# 10_-_Expansion_Connectors.net
KiCad netlist of a schematic drawn in Altium Designer
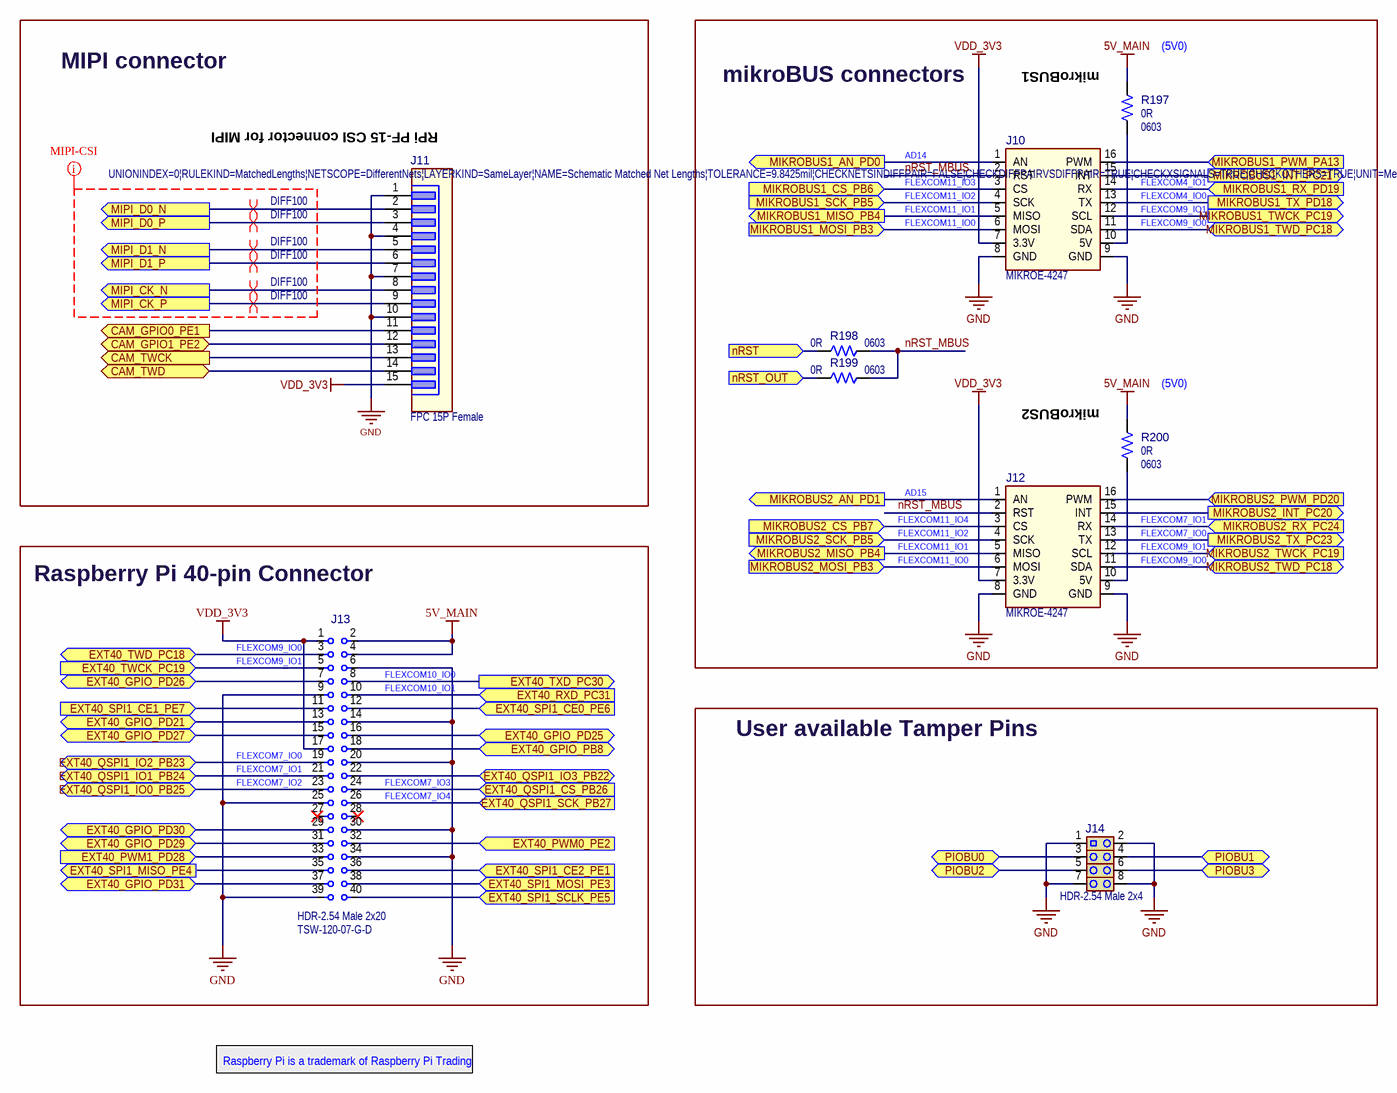
[diagram p0: 10 - Expansion Connectors.SchDoc]

(export (version "E")
  (design (tool "Eeschema 10.0.6"))
  (components
    (comp (ref "J10")
      (value "MIKROE-4247")
      (footprint "SOCKET_mikroBUS_F_2.54_2x8_V_25.4x21_original")
      (fields (field (name "Comment") "SOCKET mikroBUS HOST") (field (name "OWNER") "Dragos Danaila"))
      (libsource (lib "MCHP-CDB") (part "SOCKET mikroBUS HOST"))
    )
    (comp (ref "J11")
      (value "FPC 15P Female")
      (footprint "CON_FPC_1_FEMALE_1X15_SMD_TE_1-1734248-5")
      (fields
        (field (name "VOLTAGE") "125V")
        (field (name "Comment") "CON FPC 15pos")
        (field (name "OWNER") "Ilie Galan")
      )
      (libsource (lib "MCHP-CDB") (part "CON FPC 15pos"))
    )
    (comp (ref "J12")
      (value "MIKROE-4247")
      (footprint "SOCKET_mikroBUS_F_2.54_2x8_V_25.4x21_original")
      (fields (field (name "Comment") "SOCKET mikroBUS HOST") (field (name "OWNER") "Dragos Danaila"))
      (libsource (lib "MCHP-CDB") (part "SOCKET mikroBUS HOST"))
    )
    (comp (ref "J13")
      (value "HDR-2.54 Male 2x20")
      (footprint "HDR_M_2.54_2x20")
      (fields
        (field (name "MANUFACTURER PART NUMBER 1") "TSW-120-07-G-D")
        (field (name "Comment") "Header 2x20")
        (field (name "OWNER") "Stephen Humberd")
      )
      (libsource (lib "MCHP-CDB") (part "Header 2x20"))
    )
    (comp (ref "J14")
      (value "HDR-2.54 Male 2x4")
      (footprint "HDR_M_2.54_2x4_SMD")
      (fields (field (name "Comment") "Header 2x4") (field (name "OWNER") "Jamus Griego"))
      (libsource (lib "MCHP-CDB") (part "Header 2x4"))
    )
    (comp (ref "R197")
      (value "0R")
      (footprint "RES_C_0603")
      (description "Resistor")
      (fields (field (name "PACKAGE") "0603") (field (name "POWER") "1/10W"))
      (libsource (lib "MCHP-CDB") (part "Resistor"))
    )
    (comp (ref "R198")
      (value "0R")
      (footprint "RES_C_0603")
      (description "Resistor")
      (fields (field (name "PACKAGE") "0603") (field (name "POWER") "1/10W"))
      (libsource (lib "MCHP-CDB") (part "Resistor"))
    )
    (comp (ref "R199")
      (value "0R")
      (footprint "RES_C_0603")
      (description "Resistor")
      (fields (field (name "PACKAGE") "0603") (field (name "POWER") "1/10W"))
      (libsource (lib "MCHP-CDB") (part "Resistor"))
    )
    (comp (ref "R200")
      (value "0R")
      (footprint "RES_C_0603")
      (description "Resistor")
      (fields (field (name "PACKAGE") "0603") (field (name "POWER") "1/10W"))
      (libsource (lib "MCHP-CDB") (part "Resistor"))
    )
  )
  (nets
    (net (code "1") (name "/CAM_GPIO0_PE1") (class "Default")
      (node (ref "J11") (pin "11") (pinfunction "11_11") (pintype "passive"))
    )
    (net (code "2") (name "/CAM_GPIO1_PE2") (class "Default")
      (node (ref "J11") (pin "12") (pinfunction "12_12") (pintype "passive"))
    )
    (net (code "3") (name "/CAM_TWCK") (class "Default")
      (node (ref "J11") (pin "13") (pinfunction "13_13") (pintype "passive"))
    )
    (net (code "4") (name "/CAM_TWD") (class "Default")
      (node (ref "J11") (pin "14") (pinfunction "14_14") (pintype "passive"))
    )
    (net (code "5") (name "/EXT40_GPIO_PB8") (class "Default")
      (node (ref "J13") (pin "18") (pinfunction "18_18") (pintype "passive"))
    )
    (net (code "6") (name "/EXT40_GPIO_PD21") (class "Default")
      (node (ref "J13") (pin "13") (pinfunction "13_13") (pintype "passive"))
    )
    (net (code "7") (name "/EXT40_GPIO_PD25") (class "Default")
      (node (ref "J13") (pin "16") (pinfunction "16_16") (pintype "passive"))
    )
    (net (code "8") (name "/EXT40_GPIO_PD26") (class "Default")
      (node (ref "J13") (pin "7") (pinfunction "7_7") (pintype "passive"))
    )
    (net (code "9") (name "/EXT40_GPIO_PD27") (class "Default")
      (node (ref "J13") (pin "15") (pinfunction "15_15") (pintype "passive"))
    )
    (net (code "10") (name "/EXT40_GPIO_PD29") (class "Default")
      (node (ref "J13") (pin "31") (pinfunction "31_31") (pintype "passive"))
    )
    (net (code "11") (name "/EXT40_GPIO_PD30") (class "Default")
      (node (ref "J13") (pin "29") (pinfunction "29_29") (pintype "passive"))
    )
    (net (code "12") (name "/EXT40_GPIO_PD31") (class "Default")
      (node (ref "J13") (pin "37") (pinfunction "37_37") (pintype "passive"))
    )
    (net (code "13") (name "/EXT40_PWM0_PE2") (class "Default")
      (node (ref "J13") (pin "32") (pinfunction "32_32") (pintype "passive"))
    )
    (net (code "14") (name "/EXT40_PWM1_PD28") (class "Default")
      (node (ref "J13") (pin "33") (pinfunction "33_33") (pintype "passive"))
    )
    (net (code "15") (name "/EXT40_QSPI1_CS_PB26") (class "Default")
      (node (ref "J13") (pin "24") (pinfunction "24_24") (pintype "passive"))
    )
    (net (code "16") (name "/EXT40_QSPI1_IO0_PB25") (class "Default")
      (node (ref "J13") (pin "23") (pinfunction "23_23") (pintype "passive"))
    )
    (net (code "17") (name "/EXT40_QSPI1_IO1_PB24") (class "Default")
      (node (ref "J13") (pin "21") (pinfunction "21_21") (pintype "passive"))
    )
    (net (code "18") (name "/EXT40_QSPI1_IO2_PB23") (class "Default")
      (node (ref "J13") (pin "19") (pinfunction "19_19") (pintype "passive"))
    )
    (net (code "19") (name "/EXT40_QSPI1_IO3_PB22") (class "Default")
      (node (ref "J13") (pin "22") (pinfunction "22_22") (pintype "passive"))
    )
    (net (code "20") (name "/EXT40_QSPI1_SCK_PB27") (class "Default")
      (node (ref "J13") (pin "26") (pinfunction "26_26") (pintype "passive"))
    )
    (net (code "21") (name "/EXT40_RXD_PC31") (class "Default")
      (node (ref "J13") (pin "10") (pinfunction "10_10") (pintype "passive"))
    )
    (net (code "22") (name "/EXT40_SPI1_CE0_PE6") (class "Default")
      (node (ref "J13") (pin "12") (pinfunction "12_12") (pintype "passive"))
    )
    (net (code "23") (name "/EXT40_SPI1_CE1_PE7") (class "Default")
      (node (ref "J13") (pin "11") (pinfunction "11_11") (pintype "passive"))
    )
    (net (code "24") (name "/EXT40_SPI1_CE2_PE1") (class "Default")
      (node (ref "J13") (pin "36") (pinfunction "36_36") (pintype "passive"))
    )
    (net (code "25") (name "/EXT40_SPI1_MISO_PE4") (class "Default")
      (node (ref "J13") (pin "35") (pinfunction "35_35") (pintype "passive"))
    )
    (net (code "26") (name "/EXT40_SPI1_MOSI_PE3") (class "Default")
      (node (ref "J13") (pin "38") (pinfunction "38_38") (pintype "passive"))
    )
    (net (code "27") (name "/EXT40_SPI1_SCLK_PE5") (class "Default")
      (node (ref "J13") (pin "40") (pinfunction "40_40") (pintype "passive"))
    )
    (net (code "28") (name "/EXT40_TWCK_PC19") (class "Default")
      (node (ref "J13") (pin "5") (pinfunction "5_5") (pintype "passive"))
    )
    (net (code "29") (name "/EXT40_TWD_PC18") (class "Default")
      (node (ref "J13") (pin "3") (pinfunction "3_3") (pintype "passive"))
    )
    (net (code "30") (name "/EXT40_TXD_PC30") (class "Default")
      (node (ref "J13") (pin "8") (pinfunction "8_8") (pintype "passive"))
    )
    (net (code "31") (name "/MIKROBUS1_AN_PD0") (class "Default")
      (node (ref "J10") (pin "1") (pinfunction "AN_1") (pintype "passive"))
    )
    (net (code "32") (name "/MIKROBUS1_CS_PB6") (class "Default")
      (node (ref "J10") (pin "3") (pinfunction "CS_3") (pintype "passive"))
    )
    (net (code "33") (name "/MIKROBUS1_INT_PC21") (class "Default")
      (node (ref "J10") (pin "15") (pinfunction "INT_15") (pintype "passive"))
    )
    (net (code "34") (name "/MIKROBUS1_MISO_PB4") (class "Default")
      (node (ref "J10") (pin "5") (pinfunction "MISO_5") (pintype "passive"))
    )
    (net (code "35") (name "/MIKROBUS1_MOSI_PB3") (class "Default")
      (node (ref "J10") (pin "6") (pinfunction "MOSI_6") (pintype "passive"))
    )
    (net (code "36") (name "/MIKROBUS1_PWM_PA13") (class "Default")
      (node (ref "J10") (pin "16") (pinfunction "PWM_16") (pintype "passive"))
    )
    (net (code "37") (name "/MIKROBUS1_RX_PD19") (class "Default")
      (node (ref "J10") (pin "14") (pinfunction "RX_14") (pintype "passive"))
    )
    (net (code "38") (name "/MIKROBUS1_SCK_PB5") (class "Default")
      (node (ref "J10") (pin "4") (pinfunction "SCK_4") (pintype "passive"))
    )
    (net (code "39") (name "/MIKROBUS1_TWCK_PC19") (class "Default")
      (node (ref "J10") (pin "12") (pinfunction "SCL_12") (pintype "passive"))
    )
    (net (code "40") (name "/MIKROBUS1_TWD_PC18") (class "Default")
      (node (ref "J10") (pin "11") (pinfunction "SDA_11") (pintype "passive"))
    )
    (net (code "41") (name "/MIKROBUS1_TX_PD18") (class "Default")
      (node (ref "J10") (pin "13") (pinfunction "TX_13") (pintype "passive"))
    )
    (net (code "42") (name "/MIKROBUS2_AN_PD1") (class "Default")
      (node (ref "J12") (pin "1") (pinfunction "AN_1") (pintype "passive"))
    )
    (net (code "43") (name "/MIKROBUS2_CS_PB7") (class "Default")
      (node (ref "J12") (pin "3") (pinfunction "CS_3") (pintype "passive"))
    )
    (net (code "44") (name "/MIKROBUS2_INT_PC20") (class "Default")
      (node (ref "J12") (pin "15") (pinfunction "INT_15") (pintype "passive"))
    )
    (net (code "45") (name "/MIKROBUS2_MISO_PB4") (class "Default")
      (node (ref "J12") (pin "5") (pinfunction "MISO_5") (pintype "passive"))
    )
    (net (code "46") (name "/MIKROBUS2_MOSI_PB3") (class "Default")
      (node (ref "J12") (pin "6") (pinfunction "MOSI_6") (pintype "passive"))
    )
    (net (code "47") (name "/MIKROBUS2_PWM_PD20") (class "Default")
      (node (ref "J12") (pin "16") (pinfunction "PWM_16") (pintype "passive"))
    )
    (net (code "48") (name "/MIKROBUS2_RX_PC24") (class "Default")
      (node (ref "J12") (pin "14") (pinfunction "RX_14") (pintype "passive"))
    )
    (net (code "49") (name "/MIKROBUS2_SCK_PB5") (class "Default")
      (node (ref "J12") (pin "4") (pinfunction "SCK_4") (pintype "passive"))
    )
    (net (code "50") (name "/MIKROBUS2_TWCK_PC19") (class "Default")
      (node (ref "J12") (pin "12") (pinfunction "SCL_12") (pintype "passive"))
    )
    (net (code "51") (name "/MIKROBUS2_TWD_PC18") (class "Default")
      (node (ref "J12") (pin "11") (pinfunction "SDA_11") (pintype "passive"))
    )
    (net (code "52") (name "/MIKROBUS2_TX_PC23") (class "Default")
      (node (ref "J12") (pin "13") (pinfunction "TX_13") (pintype "passive"))
    )
    (net (code "53") (name "/MIPI_CK_N") (class "Default")
      (node (ref "J11") (pin "8") (pinfunction "8_8") (pintype "passive"))
    )
    (net (code "54") (name "/MIPI_CK_P") (class "Default")
      (node (ref "J11") (pin "9") (pinfunction "9_9") (pintype "passive"))
    )
    (net (code "55") (name "/MIPI_D0_N") (class "Default")
      (node (ref "J11") (pin "2") (pinfunction "2_2") (pintype "passive"))
    )
    (net (code "56") (name "/MIPI_D0_P") (class "Default")
      (node (ref "J11") (pin "3") (pinfunction "3_3") (pintype "passive"))
    )
    (net (code "57") (name "/MIPI_D1_N") (class "Default")
      (node (ref "J11") (pin "5") (pinfunction "5_5") (pintype "passive"))
    )
    (net (code "58") (name "/MIPI_D1_P") (class "Default")
      (node (ref "J11") (pin "6") (pinfunction "6_6") (pintype "passive"))
    )
    (net (code "59") (name "/PIOBU0") (class "Default")
      (node (ref "J14") (pin "3") (pinfunction "3_3") (pintype "passive"))
    )
    (net (code "60") (name "/PIOBU1") (class "Default")
      (node (ref "J14") (pin "4") (pinfunction "4_4") (pintype "passive"))
    )
    (net (code "61") (name "/PIOBU2") (class "Default")
      (node (ref "J14") (pin "5") (pinfunction "5_5") (pintype "passive"))
    )
    (net (code "62") (name "/PIOBU3") (class "Default")
      (node (ref "J14") (pin "6") (pinfunction "6_6") (pintype "passive"))
    )
    (net (code "63") (name "/nRST") (class "Default")
      (node (ref "R198") (pin "1") (pinfunction "1_1") (pintype "passive"))
    )
    (net (code "64") (name "/nRST_MBUS") (class "Default")
      (node (ref "J10") (pin "2") (pinfunction "RST_2") (pintype "passive"))
      (node (ref "J12") (pin "2") (pinfunction "RST_2") (pintype "passive"))
      (node (ref "R198") (pin "2") (pinfunction "2_2") (pintype "passive"))
      (node (ref "R199") (pin "2") (pinfunction "2_2") (pintype "passive"))
    )
    (net (code "65") (name "/nRST_OUT") (class "Default")
      (node (ref "R199") (pin "1") (pinfunction "1_1") (pintype "passive"))
    )
    (net (code "66") (name "5V_MAIN") (class "Default")
      (node (ref "J13") (pin "2") (pinfunction "2_2") (pintype "passive"))
      (node (ref "J13") (pin "4") (pinfunction "4_4") (pintype "passive"))
      (node (ref "R197") (pin "1") (pinfunction "1_1") (pintype "passive"))
      (node (ref "R200") (pin "1") (pinfunction "1_1") (pintype "passive"))
    )
    (net (code "67") (name "GND") (class "Default")
      (node (ref "J10") (pin "8") (pinfunction "GND_8") (pintype "passive"))
      (node (ref "J10") (pin "9") (pinfunction "GND_9") (pintype "passive"))
      (node (ref "J11") (pin "1") (pinfunction "1_1") (pintype "passive"))
      (node (ref "J11") (pin "10") (pinfunction "10_10") (pintype "passive"))
      (node (ref "J11") (pin "4") (pinfunction "4_4") (pintype "passive"))
      (node (ref "J11") (pin "7") (pinfunction "7_7") (pintype "passive"))
      (node (ref "J12") (pin "8") (pinfunction "GND_8") (pintype "passive"))
      (node (ref "J12") (pin "9") (pinfunction "GND_9") (pintype "passive"))
      (node (ref "J13") (pin "14") (pinfunction "14_14") (pintype "passive"))
      (node (ref "J13") (pin "20") (pinfunction "20_20") (pintype "passive"))
      (node (ref "J13") (pin "25") (pinfunction "25_25") (pintype "passive"))
      (node (ref "J13") (pin "30") (pinfunction "30_30") (pintype "passive"))
      (node (ref "J13") (pin "34") (pinfunction "34_34") (pintype "passive"))
      (node (ref "J13") (pin "39") (pinfunction "39_39") (pintype "passive"))
      (node (ref "J13") (pin "6") (pinfunction "6_6") (pintype "passive"))
      (node (ref "J13") (pin "9") (pinfunction "9_9") (pintype "passive"))
      (node (ref "J14") (pin "1") (pinfunction "1_1") (pintype "passive"))
      (node (ref "J14") (pin "2") (pinfunction "2_2") (pintype "passive"))
      (node (ref "J14") (pin "7") (pinfunction "7_7") (pintype "passive"))
      (node (ref "J14") (pin "8") (pinfunction "8_8") (pintype "passive"))
    )
    (net (code "68") (name "Net-(J10-5V)") (class "Default")
      (node (ref "J10") (pin "10") (pinfunction "5V_10") (pintype "passive"))
      (node (ref "R197") (pin "2") (pinfunction "2_2") (pintype "passive"))
    )
    (net (code "69") (name "Net-(J12-5V)") (class "Default")
      (node (ref "J12") (pin "10") (pinfunction "5V_10") (pintype "passive"))
      (node (ref "R200") (pin "2") (pinfunction "2_2") (pintype "passive"))
    )
    (net (code "70") (name "VDD_3V3") (class "Default")
      (node (ref "J10") (pin "7") (pinfunction "3.3V_7") (pintype "passive"))
      (node (ref "J11") (pin "15") (pinfunction "15_15") (pintype "passive"))
      (node (ref "J12") (pin "7") (pinfunction "3.3V_7") (pintype "passive"))
      (node (ref "J13") (pin "1") (pinfunction "1_1") (pintype "passive"))
      (node (ref "J13") (pin "17") (pinfunction "17_17") (pintype "passive"))
    )
    (net (code "71") (name "unconnected-(J13-Pad27)") (class "Default")
      (node (ref "J13") (pin "27") (pinfunction "27_27") (pintype "passive+no_connect"))
    )
    (net (code "72") (name "unconnected-(J13-Pad28)") (class "Default")
      (node (ref "J13") (pin "28") (pinfunction "28_28") (pintype "passive+no_connect"))
    )
  )
)
